# blink1mk3_005t6_5050_4l_usbc2020.net
KiCad netlist of a schematic drawn in EAGLE
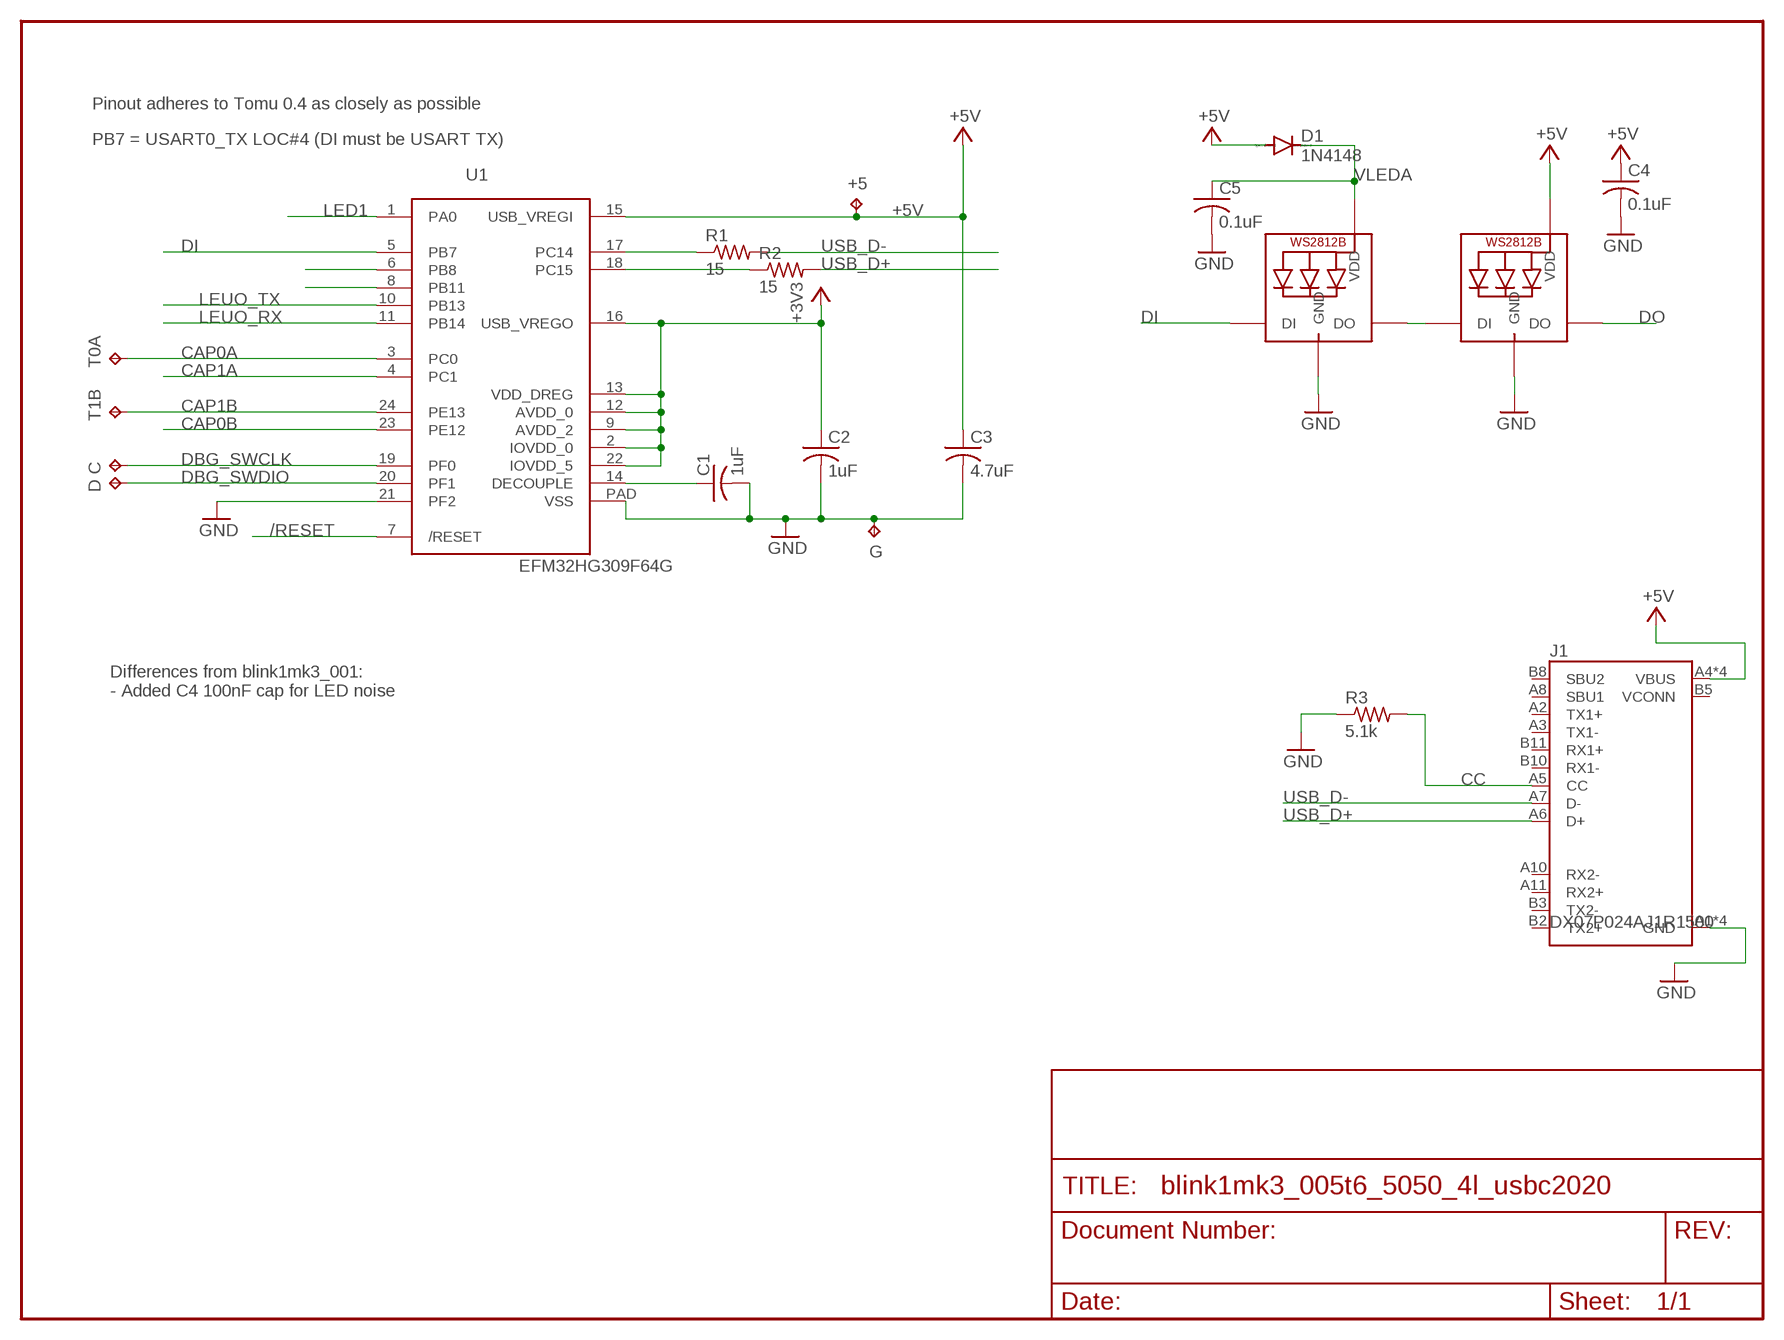
[diagram p0: schematic, sheet 1]

(export (version "E")
  (design (tool "Eeschema 10.0.6"))
  (components
    (comp (ref "+5")
      (value "TPTP10R")
      (footprint "eagle-import:TP10R")
      (libsource (lib "eagle-import") (part "TPTP10R"))
    )
    (comp (ref "C")
      (value "TPTP10R")
      (footprint "eagle-import:TP10R")
      (libsource (lib "eagle-import") (part "TPTP10R"))
    )
    (comp (ref "C1")
      (value "1uF")
      (footprint "eagle-import:C0402")
      (libsource (lib "eagle-import") (part "C-USC0402"))
    )
    (comp (ref "C2")
      (value "1uF")
      (footprint "eagle-import:C0402")
      (libsource (lib "eagle-import") (part "C-USC0402"))
    )
    (comp (ref "C3")
      (value "4.7uF")
      (footprint "eagle-import:C0402")
      (libsource (lib "eagle-import") (part "C-USC0402"))
    )
    (comp (ref "C4")
      (value "0.1uF")
      (footprint "eagle-import:C0402")
      (libsource (lib "eagle-import") (part "C-USC0402"))
    )
    (comp (ref "C5")
      (value "0.1uF")
      (footprint "eagle-import:C0402")
      (libsource (lib "eagle-import") (part "C-USC0402"))
    )
    (comp (ref "D")
      (value "TPTP10R")
      (footprint "eagle-import:TP10R")
      (libsource (lib "eagle-import") (part "TPTP10R"))
    )
    (comp (ref "D1")
      (value "1N4148")
      (footprint "eagle-import:SOD523")
      (libsource (lib "eagle-import") (part "DIODE-SOD523"))
    )
    (comp (ref "G")
      (value "TPTP10R")
      (footprint "eagle-import:TP10R")
      (libsource (lib "eagle-import") (part "TPTP10R"))
    )
    (comp (ref "J1")
      (value "DX07P024AJ1R1500")
      (footprint "eagle-import:JAE_DX07P024AJ1R1500")
      (fields (field (name "DIGI-KEY_PART_NUMBER") "670-2868-1-ND") (field (name "MF") "JAE Electronics"))
      (libsource (lib "eagle-import") (part "DX07P024AJ1R1500"))
    )
    (comp (ref "LED1")
      (value "SK6812MINI")
      (footprint "eagle-import:WS2812B")
      (libsource (lib "eagle-import") (part "WS2812B5050"))
    )
    (comp (ref "LED2")
      (value "SK6812MINI")
      (footprint "eagle-import:WS2812B")
      (libsource (lib "eagle-import") (part "WS2812B5050"))
    )
    (comp (ref "R1")
      (value "15")
      (footprint "eagle-import:R0402")
      (libsource (lib "eagle-import") (part "rcl_334_R-US_R0402"))
    )
    (comp (ref "R2")
      (value "15")
      (footprint "eagle-import:R0402")
      (libsource (lib "eagle-import") (part "rcl_334_R-US_R0402"))
    )
    (comp (ref "R3")
      (value "5.1k")
      (footprint "eagle-import:R0402")
      (libsource (lib "eagle-import") (part "R-US_R0402"))
    )
    (comp (ref "T0A")
      (value "TPTP15R")
      (footprint "eagle-import:TP15R")
      (libsource (lib "eagle-import") (part "TPTP15R"))
    )
    (comp (ref "T1B")
      (value "TPTP15R")
      (footprint "eagle-import:TP15R")
      (libsource (lib "eagle-import") (part "TPTP15R"))
    )
    (comp (ref "U1")
      (value "EFM32HG309F64G")
      (footprint "eagle-import:QFN24PAD")
      (libsource (lib "eagle-import") (part "EFM32HG309F64G"))
    )
  )
  (nets
    (net (code "1") (name "+3V3") (class "Default")
      (node (ref "C2") (pin "1") (pinfunction "1_1") (pintype "passive"))
      (node (ref "U1") (pin "12") (pinfunction "AVDD_0_12") (pintype "bidirectional"))
      (node (ref "U1") (pin "13") (pinfunction "VDD_DREG_13") (pintype "bidirectional"))
      (node (ref "U1") (pin "16") (pinfunction "USB_VREGO_16") (pintype "bidirectional"))
      (node (ref "U1") (pin "2") (pinfunction "IOVDD_0_2") (pintype "bidirectional"))
      (node (ref "U1") (pin "22") (pinfunction "IOVDD_5_22") (pintype "bidirectional"))
      (node (ref "U1") (pin "9") (pinfunction "AVDD_2_9") (pintype "bidirectional"))
    )
    (net (code "2") (name "+5V") (class "Default")
      (node (ref "+5") (pin "TP") (pinfunction "TP_TP") (pintype "input"))
      (node (ref "C3") (pin "1") (pinfunction "1_1") (pintype "passive"))
      (node (ref "C4") (pin "1") (pinfunction "1_1") (pintype "passive"))
      (node (ref "D1") (pin "A") (pinfunction "A_A") (pintype "passive"))
      (node (ref "J1") (pin "A4") (pinfunction "VBUS_A4") (pintype "power_in"))
      (node (ref "J1") (pin "A9") (pinfunction "VBUS_A9") (pintype "power_in"))
      (node (ref "J1") (pin "B4") (pinfunction "VBUS_B4") (pintype "power_in"))
      (node (ref "J1") (pin "B9") (pinfunction "VBUS_B9") (pintype "power_in"))
      (node (ref "LED2") (pin "1-VDD") (pinfunction "VDD_1-VDD") (pintype "power_in"))
      (node (ref "U1") (pin "15") (pinfunction "USB_VREGI_15") (pintype "bidirectional"))
    )
    (net (code "3") (name "/CAP0A") (class "Default")
      (node (ref "T0A") (pin "TP") (pinfunction "TP_TP") (pintype "input"))
      (node (ref "U1") (pin "3") (pinfunction "PC0_3") (pintype "bidirectional"))
    )
    (net (code "4") (name "/CAP0B") (class "Default")
      (node (ref "U1") (pin "23") (pinfunction "PE12_23") (pintype "bidirectional"))
    )
    (net (code "5") (name "/CAP1A") (class "Default")
      (node (ref "U1") (pin "4") (pinfunction "PC1_4") (pintype "bidirectional"))
    )
    (net (code "6") (name "/CAP1B") (class "Default")
      (node (ref "T1B") (pin "TP") (pinfunction "TP_TP") (pintype "input"))
      (node (ref "U1") (pin "24") (pinfunction "PE13_24") (pintype "bidirectional"))
    )
    (net (code "7") (name "/CC") (class "Default")
      (node (ref "J1") (pin "A5") (pinfunction "CC_A5") (pintype "bidirectional"))
      (node (ref "R3") (pin "2") (pinfunction "2_2") (pintype "passive"))
    )
    (net (code "8") (name "/DBG_SWCLK") (class "Default")
      (node (ref "C") (pin "TP") (pinfunction "TP_TP") (pintype "input"))
      (node (ref "U1") (pin "19") (pinfunction "PF0_19") (pintype "bidirectional"))
    )
    (net (code "9") (name "/DBG_SWDIO") (class "Default")
      (node (ref "D") (pin "TP") (pinfunction "TP_TP") (pintype "input"))
      (node (ref "U1") (pin "20") (pinfunction "PF1_20") (pintype "bidirectional"))
    )
    (net (code "10") (name "/DI") (class "Default")
      (node (ref "LED1") (pin "4-DIN") (pinfunction "DI_4-DIN") (pintype "input"))
      (node (ref "U1") (pin "5") (pinfunction "PB7_5") (pintype "bidirectional"))
    )
    (net (code "11") (name "/DO") (class "Default")
      (node (ref "LED2") (pin "2-DOUT") (pinfunction "DO_2-DOUT") (pintype "output"))
    )
    (net (code "12") (name "/LED1") (class "Default")
      (node (ref "U1") (pin "1") (pinfunction "PA0_1") (pintype "bidirectional"))
    )
    (net (code "13") (name "/LEUO_RX") (class "Default")
      (node (ref "U1") (pin "11") (pinfunction "PB14_11") (pintype "bidirectional"))
    )
    (net (code "14") (name "/LEUO_TX") (class "Default")
      (node (ref "U1") (pin "10") (pinfunction "PB13_10") (pintype "bidirectional"))
    )
    (net (code "15") (name "/USB_D+") (class "Default")
      (node (ref "J1") (pin "A6") (pinfunction "D+_A6") (pintype "bidirectional"))
      (node (ref "R2") (pin "2") (pinfunction "2_2") (pintype "passive"))
    )
    (net (code "16") (name "/USB_D-") (class "Default")
      (node (ref "J1") (pin "A7") (pinfunction "D-_A7") (pintype "bidirectional"))
      (node (ref "R1") (pin "2") (pinfunction "2_2") (pintype "passive"))
    )
    (net (code "17") (name "/VCONN") (class "Default")
      (node (ref "J1") (pin "B5") (pinfunction "VCONN_B5") (pintype "power_in"))
    )
    (net (code "18") (name "/VLEDA") (class "Default")
      (node (ref "C5") (pin "1") (pinfunction "1_1") (pintype "passive"))
      (node (ref "D1") (pin "C") (pinfunction "C_C") (pintype "passive"))
      (node (ref "LED1") (pin "1-VDD") (pinfunction "VDD_1-VDD") (pintype "power_in"))
    )
    (net (code "19") (name "/{slash}RESET") (class "Default")
      (node (ref "U1") (pin "7") (pinfunction "/RESET_7") (pintype "bidirectional"))
    )
    (net (code "20") (name "GND") (class "Default")
      (node (ref "C1") (pin "2") (pinfunction "2_2") (pintype "passive"))
      (node (ref "C2") (pin "2") (pinfunction "2_2") (pintype "passive"))
      (node (ref "C3") (pin "2") (pinfunction "2_2") (pintype "passive"))
      (node (ref "C4") (pin "2") (pinfunction "2_2") (pintype "passive"))
      (node (ref "C5") (pin "2") (pinfunction "2_2") (pintype "passive"))
      (node (ref "G") (pin "TP") (pinfunction "TP_TP") (pintype "input"))
      (node (ref "J1") (pin "A1") (pinfunction "GND_A1") (pintype "power_in"))
      (node (ref "J1") (pin "A12") (pinfunction "GND_A12") (pintype "power_in"))
      (node (ref "J1") (pin "B1") (pinfunction "GND_B1") (pintype "power_in"))
      (node (ref "J1") (pin "B12") (pinfunction "GND_B12") (pintype "power_in"))
      (node (ref "LED1") (pin "3-GND") (pinfunction "GND_3-GND") (pintype "power_in"))
      (node (ref "LED2") (pin "3-GND") (pinfunction "GND_3-GND") (pintype "power_in"))
      (node (ref "R3") (pin "1") (pinfunction "1_1") (pintype "passive"))
      (node (ref "U1") (pin "21") (pinfunction "PF2_21") (pintype "bidirectional"))
      (node (ref "U1") (pin "PAD") (pinfunction "VSS_PAD") (pintype "bidirectional"))
    )
    (net (code "21") (name "Net-(LED1-DO)") (class "Default")
      (node (ref "LED1") (pin "2-DOUT") (pinfunction "DO_2-DOUT") (pintype "output"))
      (node (ref "LED2") (pin "4-DIN") (pinfunction "DI_4-DIN") (pintype "input"))
    )
    (net (code "22") (name "Net-(U1-DECOUPLE)") (class "Default")
      (node (ref "C1") (pin "1") (pinfunction "1_1") (pintype "passive"))
      (node (ref "U1") (pin "14") (pinfunction "DECOUPLE_14") (pintype "bidirectional"))
    )
    (net (code "23") (name "Net-(U1-PC14)") (class "Default")
      (node (ref "R1") (pin "1") (pinfunction "1_1") (pintype "passive"))
      (node (ref "U1") (pin "17") (pinfunction "PC14_17") (pintype "bidirectional"))
    )
    (net (code "24") (name "Net-(U1-PC15)") (class "Default")
      (node (ref "R2") (pin "1") (pinfunction "1_1") (pintype "passive"))
      (node (ref "U1") (pin "18") (pinfunction "PC15_18") (pintype "bidirectional"))
    )
    (net (code "25") (name "unconnected-(J1-RX1+-PadB11)") (class "Default")
      (node (ref "J1") (pin "B11") (pinfunction "RX1+_B11") (pintype "bidirectional"))
    )
    (net (code "26") (name "unconnected-(J1-RX1--PadB10)") (class "Default")
      (node (ref "J1") (pin "B10") (pinfunction "RX1-_B10") (pintype "bidirectional"))
    )
    (net (code "27") (name "unconnected-(J1-RX2+-PadA11)") (class "Default")
      (node (ref "J1") (pin "A11") (pinfunction "RX2+_A11") (pintype "bidirectional"))
    )
    (net (code "28") (name "unconnected-(J1-RX2--PadA10)") (class "Default")
      (node (ref "J1") (pin "A10") (pinfunction "RX2-_A10") (pintype "bidirectional"))
    )
    (net (code "29") (name "unconnected-(J1-SBU1-PadA8)") (class "Default")
      (node (ref "J1") (pin "A8") (pinfunction "SBU1_A8") (pintype "bidirectional"))
    )
    (net (code "30") (name "unconnected-(J1-SBU2-PadB8)") (class "Default")
      (node (ref "J1") (pin "B8") (pinfunction "SBU2_B8") (pintype "bidirectional"))
    )
    (net (code "31") (name "unconnected-(J1-TX1+-PadA2)") (class "Default")
      (node (ref "J1") (pin "A2") (pinfunction "TX1+_A2") (pintype "bidirectional"))
    )
    (net (code "32") (name "unconnected-(J1-TX1--PadA3)") (class "Default")
      (node (ref "J1") (pin "A3") (pinfunction "TX1-_A3") (pintype "bidirectional"))
    )
    (net (code "33") (name "unconnected-(J1-TX2+-PadB2)") (class "Default")
      (node (ref "J1") (pin "B2") (pinfunction "TX2+_B2") (pintype "bidirectional"))
    )
    (net (code "34") (name "unconnected-(J1-TX2--PadB3)") (class "Default")
      (node (ref "J1") (pin "B3") (pinfunction "TX2-_B3") (pintype "bidirectional"))
    )
    (net (code "35") (name "unconnected-(U1-PB8-Pad6)") (class "Default")
      (node (ref "U1") (pin "6") (pinfunction "PB8_6") (pintype "bidirectional"))
    )
    (net (code "36") (name "unconnected-(U1-PB11-Pad8)") (class "Default")
      (node (ref "U1") (pin "8") (pinfunction "PB11_8") (pintype "bidirectional"))
    )
  )
)
